# LM334_Constant_Current_Source.net
KiCad netlist of a schematic drawn in Altium Designer
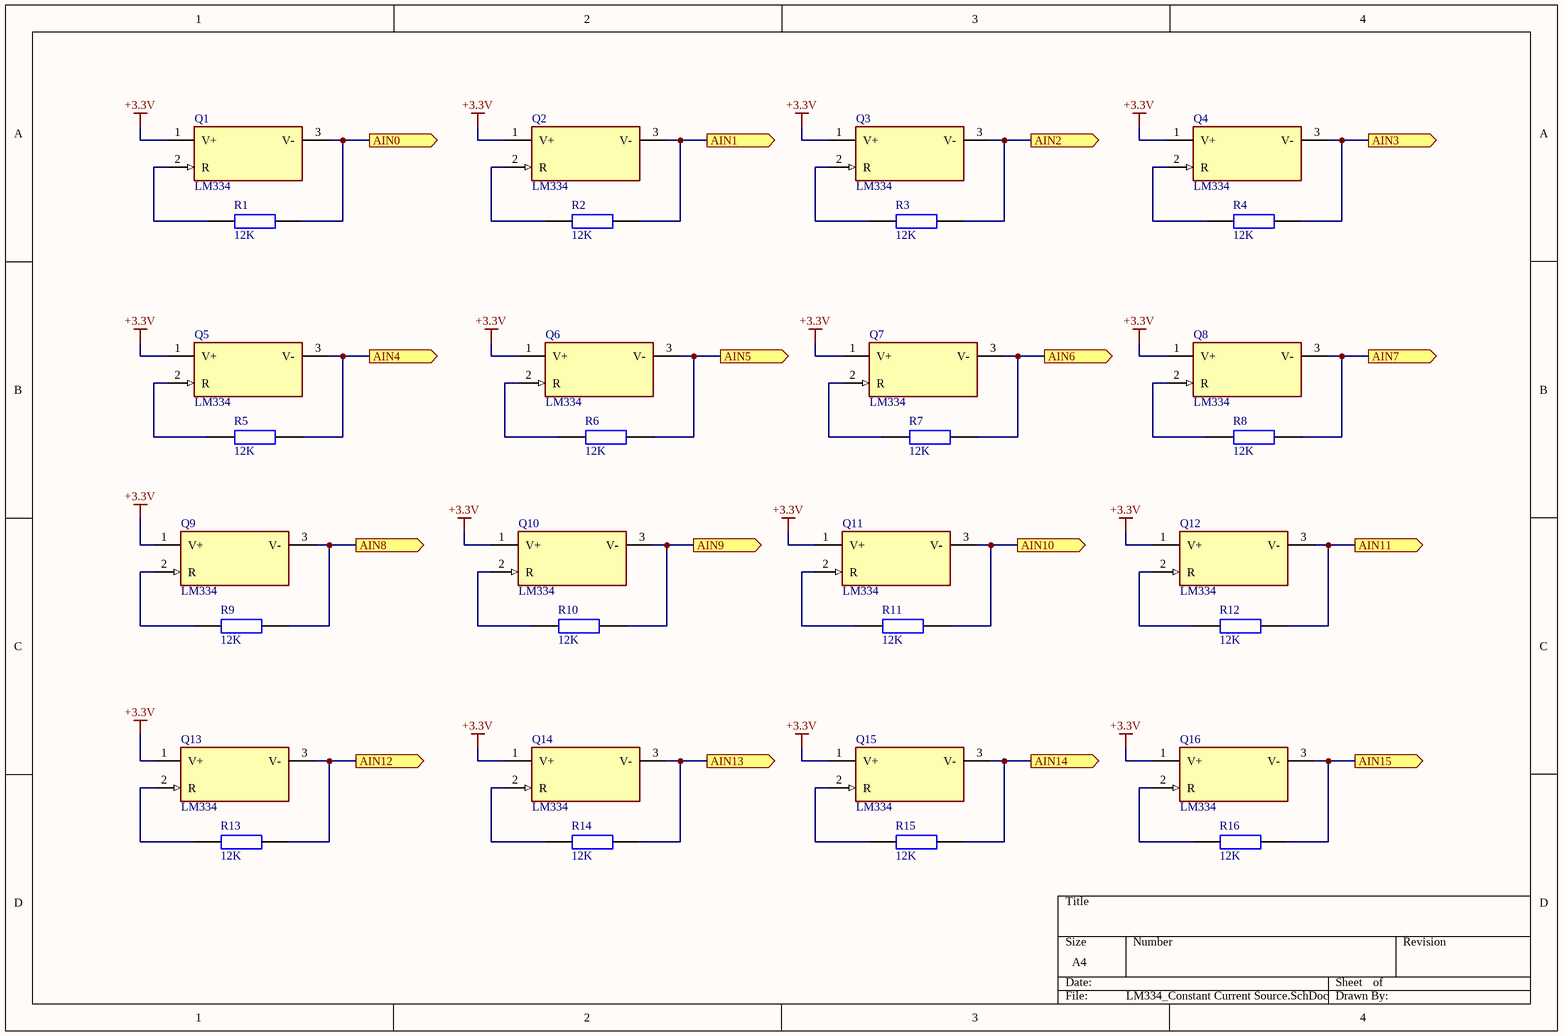
[diagram p0: LM334_Constant Current Source.SchDoc]

(export (version "E")
  (design (tool "Eeschema 10.0.6"))
  (components
    (comp (ref "Q1")
      (value "LM334")
      (footprint "LM334_TO-92")
      (libsource (lib "CV-R-BAP_V2.1.5") (part "LM334"))
    )
    (comp (ref "Q2")
      (value "LM334")
      (footprint "LM334_TO-92")
      (libsource (lib "CV-R-BAP_V2.1.5") (part "LM334"))
    )
    (comp (ref "Q3")
      (value "LM334")
      (footprint "LM334_TO-92")
      (libsource (lib "CV-R-BAP_V2.1.5") (part "LM334"))
    )
    (comp (ref "Q4")
      (value "LM334")
      (footprint "LM334_TO-92")
      (libsource (lib "CV-R-BAP_V2.1.5") (part "LM334"))
    )
    (comp (ref "Q5")
      (value "LM334")
      (footprint "LM334_TO-92")
      (libsource (lib "CV-R-BAP_V2.1.5") (part "LM334"))
    )
    (comp (ref "Q6")
      (value "LM334")
      (footprint "LM334_TO-92")
      (libsource (lib "CV-R-BAP_V2.1.5") (part "LM334"))
    )
    (comp (ref "Q7")
      (value "LM334")
      (footprint "LM334_TO-92")
      (libsource (lib "CV-R-BAP_V2.1.5") (part "LM334"))
    )
    (comp (ref "Q8")
      (value "LM334")
      (footprint "LM334_TO-92")
      (libsource (lib "CV-R-BAP_V2.1.5") (part "LM334"))
    )
    (comp (ref "Q9")
      (value "LM334")
      (footprint "LM334_TO-92")
      (libsource (lib "CV-R-BAP_V2.1.5") (part "LM334"))
    )
    (comp (ref "Q10")
      (value "LM334")
      (footprint "LM334_TO-92")
      (libsource (lib "CV-R-BAP_V2.1.5") (part "LM334"))
    )
    (comp (ref "Q11")
      (value "LM334")
      (footprint "LM334_TO-92")
      (libsource (lib "CV-R-BAP_V2.1.5") (part "LM334"))
    )
    (comp (ref "Q12")
      (value "LM334")
      (footprint "LM334_TO-92")
      (libsource (lib "CV-R-BAP_V2.1.5") (part "LM334"))
    )
    (comp (ref "Q13")
      (value "LM334")
      (footprint "LM334_TO-92")
      (libsource (lib "CV-R-BAP_V2.1.5") (part "LM334"))
    )
    (comp (ref "Q14")
      (value "LM334")
      (footprint "LM334_TO-92")
      (libsource (lib "CV-R-BAP_V2.1.5") (part "LM334"))
    )
    (comp (ref "Q15")
      (value "LM334")
      (footprint "LM334_TO-92")
      (libsource (lib "CV-R-BAP_V2.1.5") (part "LM334"))
    )
    (comp (ref "Q16")
      (value "LM334")
      (footprint "LM334_TO-92")
      (libsource (lib "CV-R-BAP_V2.1.5") (part "LM334"))
    )
    (comp (ref "R1")
      (value "12K")
      (footprint "RESC1608X55N")
      (description "YAGEO (PHYCOMP) - RC0603FR-0712KL - RES, THICK FILM, 12K, 1%, 0.1W, 0603")
      (libsource (lib "330E_0603") (part "RC0603FR-07330RL"))
    )
    (comp (ref "R2")
      (value "12K")
      (footprint "RESC1608X55N")
      (description "YAGEO (PHYCOMP) - RC0603FR-0712KL - RES, THICK FILM, 12K, 1%, 0.1W, 0603")
      (libsource (lib "330E_0603") (part "RC0603FR-07330RL"))
    )
    (comp (ref "R3")
      (value "12K")
      (footprint "RESC1608X55N")
      (description "YAGEO (PHYCOMP) - RC0603FR-0712KL - RES, THICK FILM, 12K, 1%, 0.1W, 0603")
      (libsource (lib "330E_0603") (part "RC0603FR-07330RL"))
    )
    (comp (ref "R4")
      (value "12K")
      (footprint "RESC1608X55N")
      (description "YAGEO (PHYCOMP) - RC0603FR-0712KL - RES, THICK FILM, 12K, 1%, 0.1W, 0603")
      (libsource (lib "330E_0603") (part "RC0603FR-07330RL"))
    )
    (comp (ref "R5")
      (value "12K")
      (footprint "RESC1608X55N")
      (description "YAGEO (PHYCOMP) - RC0603FR-0712KL - RES, THICK FILM, 12K, 1%, 0.1W, 0603")
      (libsource (lib "330E_0603") (part "RC0603FR-07330RL"))
    )
    (comp (ref "R6")
      (value "12K")
      (footprint "RESC1608X55N")
      (description "YAGEO (PHYCOMP) - RC0603FR-0712KL - RES, THICK FILM, 12K, 1%, 0.1W, 0603")
      (libsource (lib "330E_0603") (part "RC0603FR-07330RL"))
    )
    (comp (ref "R7")
      (value "12K")
      (footprint "RESC1608X55N")
      (description "YAGEO (PHYCOMP) - RC0603FR-0712KL - RES, THICK FILM, 12K, 1%, 0.1W, 0603")
      (libsource (lib "330E_0603") (part "RC0603FR-07330RL"))
    )
    (comp (ref "R8")
      (value "12K")
      (footprint "RESC1608X55N")
      (description "YAGEO (PHYCOMP) - RC0603FR-0712KL - RES, THICK FILM, 12K, 1%, 0.1W, 0603")
      (libsource (lib "330E_0603") (part "RC0603FR-07330RL"))
    )
    (comp (ref "R9")
      (value "12K")
      (footprint "RESC1608X55N")
      (description "YAGEO (PHYCOMP) - RC0603FR-0712KL - RES, THICK FILM, 12K, 1%, 0.1W, 0603")
      (libsource (lib "330E_0603") (part "RC0603FR-07330RL"))
    )
    (comp (ref "R10")
      (value "12K")
      (footprint "RESC1608X55N")
      (description "YAGEO (PHYCOMP) - RC0603FR-0712KL - RES, THICK FILM, 12K, 1%, 0.1W, 0603")
      (libsource (lib "330E_0603") (part "RC0603FR-07330RL"))
    )
    (comp (ref "R11")
      (value "12K")
      (footprint "RESC1608X55N")
      (description "YAGEO (PHYCOMP) - RC0603FR-0712KL - RES, THICK FILM, 12K, 1%, 0.1W, 0603")
      (libsource (lib "330E_0603") (part "RC0603FR-07330RL"))
    )
    (comp (ref "R12")
      (value "12K")
      (footprint "RESC1608X55N")
      (description "YAGEO (PHYCOMP) - RC0603FR-0712KL - RES, THICK FILM, 12K, 1%, 0.1W, 0603")
      (libsource (lib "330E_0603") (part "RC0603FR-07330RL"))
    )
    (comp (ref "R13")
      (value "12K")
      (footprint "RESC1608X55N")
      (description "YAGEO (PHYCOMP) - RC0603FR-0712KL - RES, THICK FILM, 12K, 1%, 0.1W, 0603")
      (libsource (lib "330E_0603") (part "RC0603FR-07330RL"))
    )
    (comp (ref "R14")
      (value "12K")
      (footprint "RESC1608X55N")
      (description "YAGEO (PHYCOMP) - RC0603FR-0712KL - RES, THICK FILM, 12K, 1%, 0.1W, 0603")
      (libsource (lib "330E_0603") (part "RC0603FR-07330RL"))
    )
    (comp (ref "R15")
      (value "12K")
      (footprint "RESC1608X55N")
      (description "YAGEO (PHYCOMP) - RC0603FR-0712KL - RES, THICK FILM, 12K, 1%, 0.1W, 0603")
      (libsource (lib "330E_0603") (part "RC0603FR-07330RL"))
    )
    (comp (ref "R16")
      (value "12K")
      (footprint "RESC1608X55N")
      (description "YAGEO (PHYCOMP) - RC0603FR-0712KL - RES, THICK FILM, 12K, 1%, 0.1W, 0603")
      (libsource (lib "330E_0603") (part "RC0603FR-07330RL"))
    )
  )
  (nets
    (net (code "1") (name "+3.3V") (class "Default")
      (node (ref "Q1") (pin "1") (pinfunction "V+_1") (pintype "power_in"))
      (node (ref "Q10") (pin "1") (pinfunction "V+_1") (pintype "power_in"))
      (node (ref "Q11") (pin "1") (pinfunction "V+_1") (pintype "power_in"))
      (node (ref "Q12") (pin "1") (pinfunction "V+_1") (pintype "power_in"))
      (node (ref "Q13") (pin "1") (pinfunction "V+_1") (pintype "power_in"))
      (node (ref "Q14") (pin "1") (pinfunction "V+_1") (pintype "power_in"))
      (node (ref "Q15") (pin "1") (pinfunction "V+_1") (pintype "power_in"))
      (node (ref "Q16") (pin "1") (pinfunction "V+_1") (pintype "power_in"))
      (node (ref "Q2") (pin "1") (pinfunction "V+_1") (pintype "power_in"))
      (node (ref "Q3") (pin "1") (pinfunction "V+_1") (pintype "power_in"))
      (node (ref "Q4") (pin "1") (pinfunction "V+_1") (pintype "power_in"))
      (node (ref "Q5") (pin "1") (pinfunction "V+_1") (pintype "power_in"))
      (node (ref "Q6") (pin "1") (pinfunction "V+_1") (pintype "power_in"))
      (node (ref "Q7") (pin "1") (pinfunction "V+_1") (pintype "power_in"))
      (node (ref "Q8") (pin "1") (pinfunction "V+_1") (pintype "power_in"))
      (node (ref "Q9") (pin "1") (pinfunction "V+_1") (pintype "power_in"))
    )
    (net (code "2") (name "/AIN0") (class "Default")
      (node (ref "Q1") (pin "3") (pinfunction "V-_3") (pintype "passive"))
      (node (ref "R1") (pin "1") (pinfunction "1_1") (pintype "passive"))
    )
    (net (code "3") (name "/AIN1") (class "Default")
      (node (ref "Q2") (pin "3") (pinfunction "V-_3") (pintype "passive"))
      (node (ref "R2") (pin "1") (pinfunction "1_1") (pintype "passive"))
    )
    (net (code "4") (name "/AIN2") (class "Default")
      (node (ref "Q3") (pin "3") (pinfunction "V-_3") (pintype "passive"))
      (node (ref "R3") (pin "1") (pinfunction "1_1") (pintype "passive"))
    )
    (net (code "5") (name "/AIN3") (class "Default")
      (node (ref "Q4") (pin "3") (pinfunction "V-_3") (pintype "passive"))
      (node (ref "R4") (pin "1") (pinfunction "1_1") (pintype "passive"))
    )
    (net (code "6") (name "/AIN4") (class "Default")
      (node (ref "Q5") (pin "3") (pinfunction "V-_3") (pintype "passive"))
      (node (ref "R5") (pin "1") (pinfunction "1_1") (pintype "passive"))
    )
    (net (code "7") (name "/AIN5") (class "Default")
      (node (ref "Q6") (pin "3") (pinfunction "V-_3") (pintype "passive"))
      (node (ref "R6") (pin "1") (pinfunction "1_1") (pintype "passive"))
    )
    (net (code "8") (name "/AIN6") (class "Default")
      (node (ref "Q7") (pin "3") (pinfunction "V-_3") (pintype "passive"))
      (node (ref "R7") (pin "1") (pinfunction "1_1") (pintype "passive"))
    )
    (net (code "9") (name "/AIN7") (class "Default")
      (node (ref "Q8") (pin "3") (pinfunction "V-_3") (pintype "passive"))
      (node (ref "R8") (pin "1") (pinfunction "1_1") (pintype "passive"))
    )
    (net (code "10") (name "/AIN8") (class "Default")
      (node (ref "Q9") (pin "3") (pinfunction "V-_3") (pintype "passive"))
      (node (ref "R9") (pin "1") (pinfunction "1_1") (pintype "passive"))
    )
    (net (code "11") (name "/AIN9") (class "Default")
      (node (ref "Q10") (pin "3") (pinfunction "V-_3") (pintype "passive"))
      (node (ref "R10") (pin "1") (pinfunction "1_1") (pintype "passive"))
    )
    (net (code "12") (name "/AIN10") (class "Default")
      (node (ref "Q11") (pin "3") (pinfunction "V-_3") (pintype "passive"))
      (node (ref "R11") (pin "1") (pinfunction "1_1") (pintype "passive"))
    )
    (net (code "13") (name "/AIN11") (class "Default")
      (node (ref "Q12") (pin "3") (pinfunction "V-_3") (pintype "passive"))
      (node (ref "R12") (pin "1") (pinfunction "1_1") (pintype "passive"))
    )
    (net (code "14") (name "/AIN12") (class "Default")
      (node (ref "Q13") (pin "3") (pinfunction "V-_3") (pintype "passive"))
      (node (ref "R13") (pin "1") (pinfunction "1_1") (pintype "passive"))
    )
    (net (code "15") (name "/AIN13") (class "Default")
      (node (ref "Q14") (pin "3") (pinfunction "V-_3") (pintype "passive"))
      (node (ref "R14") (pin "1") (pinfunction "1_1") (pintype "passive"))
    )
    (net (code "16") (name "/AIN14") (class "Default")
      (node (ref "Q15") (pin "3") (pinfunction "V-_3") (pintype "passive"))
      (node (ref "R15") (pin "1") (pinfunction "1_1") (pintype "passive"))
    )
    (net (code "17") (name "/AIN15") (class "Default")
      (node (ref "Q16") (pin "3") (pinfunction "V-_3") (pintype "passive"))
      (node (ref "R16") (pin "1") (pinfunction "1_1") (pintype "passive"))
    )
    (net (code "18") (name "Net-(Q1-R)") (class "Default")
      (node (ref "Q1") (pin "2") (pinfunction "R_2") (pintype "input"))
      (node (ref "R1") (pin "2") (pinfunction "2_2") (pintype "passive"))
    )
    (net (code "19") (name "Net-(Q2-R)") (class "Default")
      (node (ref "Q2") (pin "2") (pinfunction "R_2") (pintype "input"))
      (node (ref "R2") (pin "2") (pinfunction "2_2") (pintype "passive"))
    )
    (net (code "20") (name "Net-(Q3-R)") (class "Default")
      (node (ref "Q3") (pin "2") (pinfunction "R_2") (pintype "input"))
      (node (ref "R3") (pin "2") (pinfunction "2_2") (pintype "passive"))
    )
    (net (code "21") (name "Net-(Q4-R)") (class "Default")
      (node (ref "Q4") (pin "2") (pinfunction "R_2") (pintype "input"))
      (node (ref "R4") (pin "2") (pinfunction "2_2") (pintype "passive"))
    )
    (net (code "22") (name "Net-(Q5-R)") (class "Default")
      (node (ref "Q5") (pin "2") (pinfunction "R_2") (pintype "input"))
      (node (ref "R5") (pin "2") (pinfunction "2_2") (pintype "passive"))
    )
    (net (code "23") (name "Net-(Q6-R)") (class "Default")
      (node (ref "Q6") (pin "2") (pinfunction "R_2") (pintype "input"))
      (node (ref "R6") (pin "2") (pinfunction "2_2") (pintype "passive"))
    )
    (net (code "24") (name "Net-(Q7-R)") (class "Default")
      (node (ref "Q7") (pin "2") (pinfunction "R_2") (pintype "input"))
      (node (ref "R7") (pin "2") (pinfunction "2_2") (pintype "passive"))
    )
    (net (code "25") (name "Net-(Q8-R)") (class "Default")
      (node (ref "Q8") (pin "2") (pinfunction "R_2") (pintype "input"))
      (node (ref "R8") (pin "2") (pinfunction "2_2") (pintype "passive"))
    )
    (net (code "26") (name "Net-(Q9-R)") (class "Default")
      (node (ref "Q9") (pin "2") (pinfunction "R_2") (pintype "input"))
      (node (ref "R9") (pin "2") (pinfunction "2_2") (pintype "passive"))
    )
    (net (code "27") (name "Net-(Q10-R)") (class "Default")
      (node (ref "Q10") (pin "2") (pinfunction "R_2") (pintype "input"))
      (node (ref "R10") (pin "2") (pinfunction "2_2") (pintype "passive"))
    )
    (net (code "28") (name "Net-(Q11-R)") (class "Default")
      (node (ref "Q11") (pin "2") (pinfunction "R_2") (pintype "input"))
      (node (ref "R11") (pin "2") (pinfunction "2_2") (pintype "passive"))
    )
    (net (code "29") (name "Net-(Q12-R)") (class "Default")
      (node (ref "Q12") (pin "2") (pinfunction "R_2") (pintype "input"))
      (node (ref "R12") (pin "2") (pinfunction "2_2") (pintype "passive"))
    )
    (net (code "30") (name "Net-(Q13-R)") (class "Default")
      (node (ref "Q13") (pin "2") (pinfunction "R_2") (pintype "input"))
      (node (ref "R13") (pin "2") (pinfunction "2_2") (pintype "passive"))
    )
    (net (code "31") (name "Net-(Q14-R)") (class "Default")
      (node (ref "Q14") (pin "2") (pinfunction "R_2") (pintype "input"))
      (node (ref "R14") (pin "2") (pinfunction "2_2") (pintype "passive"))
    )
    (net (code "32") (name "Net-(Q15-R)") (class "Default")
      (node (ref "Q15") (pin "2") (pinfunction "R_2") (pintype "input"))
      (node (ref "R15") (pin "2") (pinfunction "2_2") (pintype "passive"))
    )
    (net (code "33") (name "Net-(Q16-R)") (class "Default")
      (node (ref "Q16") (pin "2") (pinfunction "R_2") (pintype "input"))
      (node (ref "R16") (pin "2") (pinfunction "2_2") (pintype "passive"))
    )
  )
)
